# Accessories.net
KiCad netlist of a schematic drawn in Altium Designer
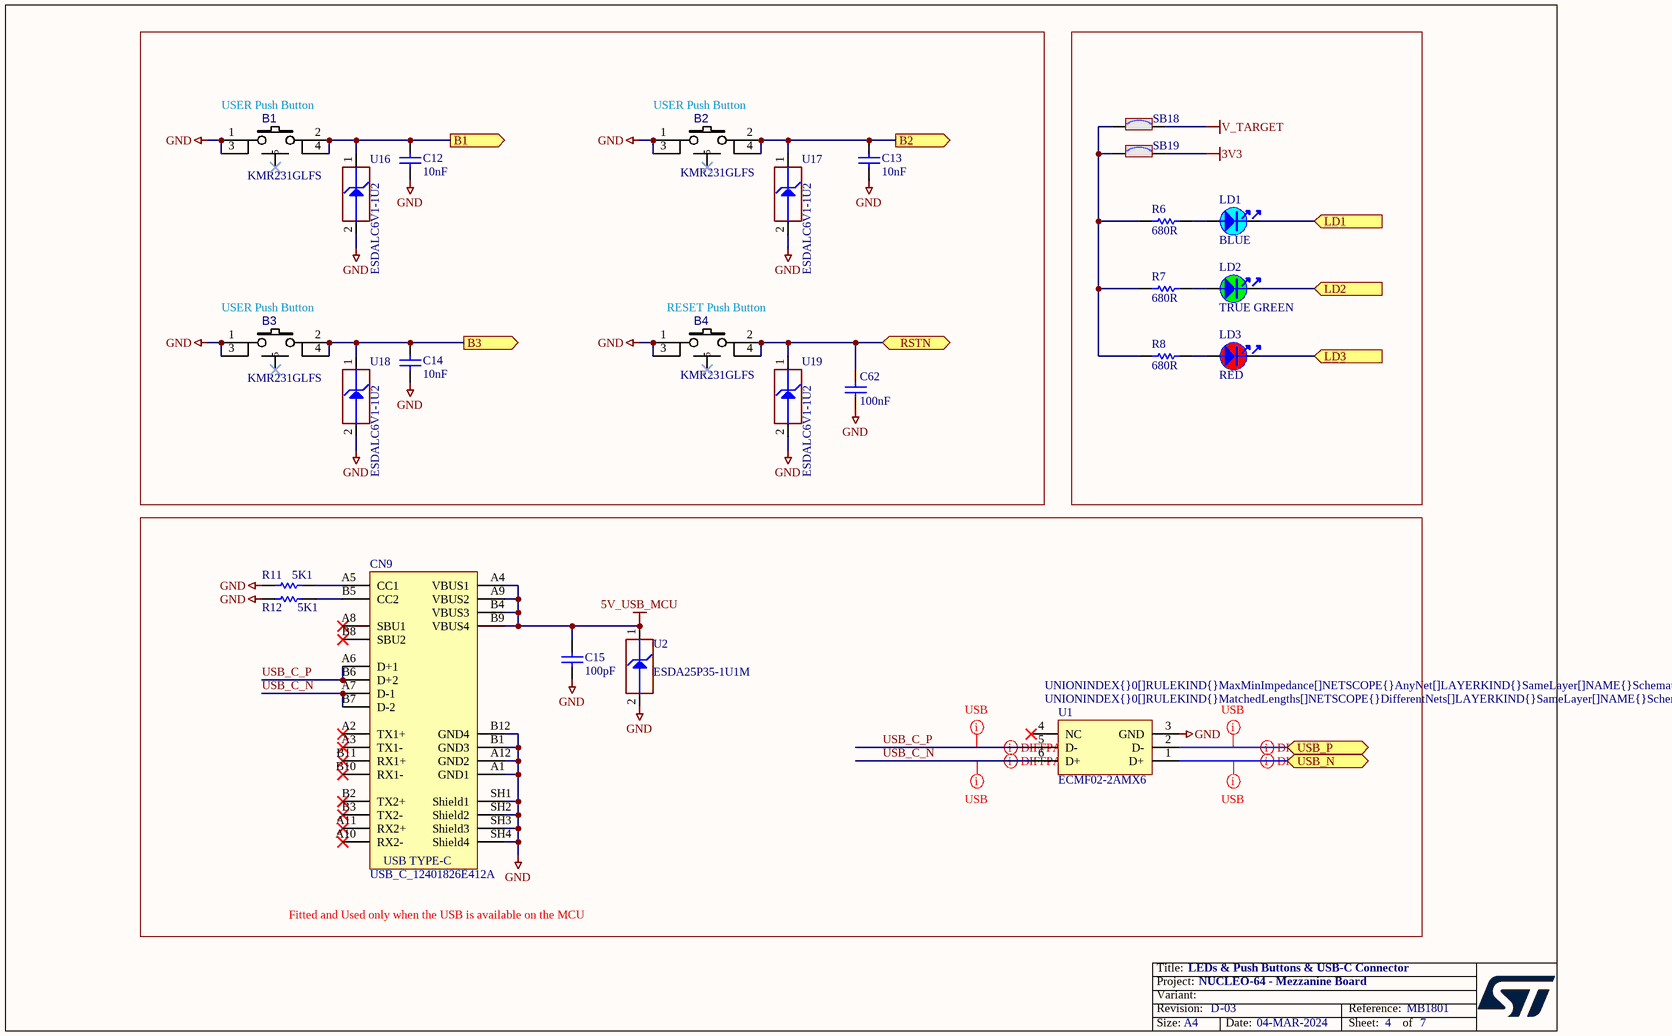
[diagram p0: Accessories.SchDoc]

(export (version "E")
  (design (tool "Eeschema 10.0.6"))
  (components
    (comp (ref "B1")
      (value "KMR231GLFS")
      (footprint "MCD_PARTS:SWI_C&K_Y78B23110FP__ITT_KMR231GLFS")
      (description "Microminiature Tact Switch for SMT - KMR 2 Series - 1.9 mm height")
      (fields (field (name "INTERNAL_PART_NUMBER") "MCD-01485") (field (name "MANUFACTURER") "C&K"))
      (libsource (lib "MCD_PARTS_database") (part "SW-PUSH-CMS_KMR2_BLACK"))
    )
    (comp (ref "B2")
      (value "KMR231GLFS")
      (footprint "MCD_PARTS:SWI_C&K_Y78B23110FP__ITT_KMR231GLFS")
      (description "Microminiature Tact Switch for SMT - KMR 2 Series - 1.9 mm height")
      (fields (field (name "INTERNAL_PART_NUMBER") "MCD-01485") (field (name "MANUFACTURER") "C&K"))
      (libsource (lib "MCD_PARTS_database") (part "SW-PUSH-CMS_KMR2_BLACK"))
    )
    (comp (ref "B3")
      (value "KMR231GLFS")
      (footprint "MCD_PARTS:SWI_C&K_Y78B23110FP__ITT_KMR231GLFS")
      (description "Microminiature Tact Switch for SMT - KMR 2 Series - 1.9 mm height")
      (fields (field (name "INTERNAL_PART_NUMBER") "MCD-01485") (field (name "MANUFACTURER") "C&K"))
      (libsource (lib "MCD_PARTS_database") (part "SW-PUSH-CMS_KMR2_BLACK"))
    )
    (comp (ref "B4")
      (value "KMR231GLFS")
      (footprint "MCD_PARTS:SWI_C&K_Y78B23110FP__ITT_KMR231GLFS")
      (description "Microminiature Tact Switch for SMT - KMR 2 Series - 1.9 mm height")
      (fields (field (name "INTERNAL_PART_NUMBER") "MCD-01485") (field (name "MANUFACTURER") "C&K"))
      (libsource (lib "MCD_PARTS_database") (part "SW-PUSH-CMS_KMR2_BLACK"))
    )
    (comp (ref "C12")
      (value "10nF")
      (footprint "MCD_PARTS:C0402")
      (description "Capacitor, MLCC, 10nF, 50V, X7R, +/-10%, 0402, T=0.5mm")
      (fields (field (name "INTERNAL_PART_NUMBER") "MCD-02198") (field (name "MANUFACTURER") "YAGEO"))
      (libsource (lib "MCD_PARTS_database") (part "Capacitor"))
    )
    (comp (ref "C13")
      (value "10nF")
      (footprint "MCD_PARTS:C0402")
      (description "Capacitor, MLCC, 10nF, 50V, X7R, +/-10%, 0402, T=0.5mm")
      (fields (field (name "INTERNAL_PART_NUMBER") "MCD-02198") (field (name "MANUFACTURER") "YAGEO"))
      (libsource (lib "MCD_PARTS_database") (part "Capacitor"))
    )
    (comp (ref "C14")
      (value "10nF")
      (footprint "MCD_PARTS:C0402")
      (description "Capacitor, MLCC, 10nF, 50V, X7R, +/-10%, 0402, T=0.5mm")
      (fields (field (name "INTERNAL_PART_NUMBER") "MCD-02198") (field (name "MANUFACTURER") "YAGEO"))
      (libsource (lib "MCD_PARTS_database") (part "Capacitor"))
    )
    (comp (ref "C15")
      (value "100pF")
      (footprint "MCD_PARTS:C0402")
      (description "Capacitor, MLCC, 100pF, 50V, NPO, +/-5%, 0402, T=0.5mm")
      (fields
        (field (name "INTERNAL_PART_NUMBER") "MCD-00205")
        (field (name "MANUFACTURER_PART_NUMBER") "CC0402JRNPO9BN101")
      )
      (libsource (lib "MCD_PARTS_database") (part "Capacitor"))
    )
    (comp (ref "C62")
      (value "100nF")
      (footprint "C0402")
      (description "Capacitor, MLCC, 100nF, 16V, X7R, 10%, 0402, T=0.5mm")
      (fields
        (field (name "INTERNAL_PART_NUMBER") "MCD-00006")
        (field (name "MANUFACTURER_PART_NUMBER") "CC0402KRX7R7BB104")
        (field (name "PROVIDED_BY") "SUBCO")
      )
      (libsource (lib "MCD_PARTS_database") (part "Capacitor"))
    )
    (comp (ref "CN9")
      (value "USB_C_12401826E412A")
      (footprint "MCD_PARTS:CON_USB-TYPEC_AMPHENOL_12401826E412A")
      (description "USB_TypeC, 24 pins, RA, SMD, T=2.96mm")
      (fields (field (name "INTERNAL_PART_NUMBER") "MCD-03232") (field (name "MANUFACTURER") "AMPHENOL ICC"))
      (libsource (lib "MCD_PARTS_database") (part "USB_TYPE_C_Receptacle"))
    )
    (comp (ref "LD1")
      (value "BLUE")
      (footprint "MCD_PARTS:LED_0603_VISHAY_VLMB1300-GS08_BLUE_1A2K_H0P8")
      (description "LED Blue, 0603 SMD, 3.3 V Forward Voltage")
      (fields
        (field (name "INTERNAL_PART_NUMBER") "MCD-00584")
        (field (name "MANUFACTURER_PART_NUMBER") "VLMB1300-GS08")
      )
      (libsource (lib "MCD_PARTS_database") (part "LED_blue"))
    )
    (comp (ref "LD2")
      (value "TRUE GREEN")
      (footprint "MCD_PARTS:LED_0603_VISHAY_VLMTG1300-GS08_GREEN_1A2K_H0P8")
      (description "LED Green, 0603 SMD, Fw Voltage = 2.8V - 3.6V")
      (fields
        (field (name "INTERNAL_PART_NUMBER") "MCD-00589")
        (field (name "MANUFACTURER_PART_NUMBER") "VLMTG1300-GS08")
      )
      (libsource (lib "MCD_PARTS_database") (part "LED_green"))
    )
    (comp (ref "LD3")
      (value "RED")
      (footprint "MCD_PARTS:LED_0603_VISHAY_VLMS1300-GS08_RED_1A2K_H0P8")
      (description "LED Red, 0603 SMD, 2V Forward Voltage")
      (fields
        (field (name "INTERNAL_PART_NUMBER") "MCD-00587")
        (field (name "MANUFACTURER_PART_NUMBER") "VLMS1300-GS08")
      )
      (libsource (lib "MCD_PARTS_database") (part "LED_red"))
    )
    (comp (ref "R6")
      (value "680R")
      (footprint "MCD_PARTS:R0402")
      (description "Resistor, 680R, 0402, +/-1%, 1/16W")
      (fields
        (field (name "INTERNAL_PART_NUMBER") "MCD-00507")
        (field (name "MANUFACTURER_PART_NUMBER") "RC0402FR-07680RL")
      )
      (libsource (lib "MCD_PARTS_database") (part "Resistor"))
    )
    (comp (ref "R7")
      (value "680R")
      (footprint "MCD_PARTS:R0402")
      (description "Resistor, 680R, 0402, +/-1%, 1/16W")
      (fields
        (field (name "INTERNAL_PART_NUMBER") "MCD-00507")
        (field (name "MANUFACTURER_PART_NUMBER") "RC0402FR-07680RL")
      )
      (libsource (lib "MCD_PARTS_database") (part "Resistor"))
    )
    (comp (ref "R8")
      (value "680R")
      (footprint "MCD_PARTS:R0402")
      (description "Resistor, 680R, 0402, +/-1%, 1/16W")
      (fields
        (field (name "INTERNAL_PART_NUMBER") "MCD-00507")
        (field (name "MANUFACTURER_PART_NUMBER") "RC0402FR-07680RL")
      )
      (libsource (lib "MCD_PARTS_database") (part "Resistor"))
    )
    (comp (ref "R11")
      (value "5K1")
      (footprint "MCD_PARTS:R0402")
      (description "Resistor, 5K1, 0402, +/-1%, 1/16W")
      (fields
        (field (name "INTERNAL_PART_NUMBER") "MCD-00333")
        (field (name "MANUFACTURER_PART_NUMBER") "RC0402FR-075K1L")
      )
      (libsource (lib "MCD_PARTS_database") (part "Resistor"))
    )
    (comp (ref "R12")
      (value "5K1")
      (footprint "MCD_PARTS:R0402")
      (description "Resistor, 5K1, 0402, +/-1%, 1/16W")
      (fields
        (field (name "INTERNAL_PART_NUMBER") "MCD-00333")
        (field (name "MANUFACTURER_PART_NUMBER") "RC0402FR-075K1L")
      )
      (libsource (lib "MCD_PARTS_database") (part "Resistor"))
    )
    (comp (ref "SB18")
      (value "SB_ON")
      (footprint "MCD_PARTS:SOLDER-BRIDGE_R0402-0R")
      (description "Solder Bridge 0402 ON")
      (fields (field (name "INTERNAL_PART_NUMBER") "MCD-01618") (field (name "MANUFACTURER") "YAGEO"))
      (libsource (lib "MCD_PARTS_database") (part "SB_ON"))
    )
    (comp (ref "SB19")
      (value "SB_ON")
      (footprint "MCD_PARTS:SOLDER-BRIDGE_R0402-0R")
      (description "Solder Bridge 0402 ON")
      (fields (field (name "INTERNAL_PART_NUMBER") "MCD-01618") (field (name "MANUFACTURER") "YAGEO"))
      (libsource (lib "MCD_PARTS_database") (part "SB_ON"))
    )
    (comp (ref "U1")
      (value "ECMF02-2AMX6")
      (footprint "MCD_PARTS:ESD_QFN-6L_1P7X1P5_P050")
      (description "Common mode filter with ESD protection for USB 2.0 interface")
      (fields
        (field (name "INTERNAL_PART_NUMBER") "MCD-00649")
        (field (name "MANUFACTURER") "STMICROELECTRONICS")
      )
      (libsource (lib "MCD_PARTS_database") (part "ECMF02-2AMX6"))
    )
    (comp (ref "U2")
      (value "ESDA25P35-1U1M")
      (footprint "MCD_PARTS:ESD_QFN1610_2N_1K_2A")
      (description "High power Transient voltage suppressor:25V/35A EOS and ESD transients protection.")
      (fields
        (field (name "INTERNAL_PART_NUMBER") "MCD-01207")
        (field (name "MANUFACTURER") "STMICROELECTRONICS")
      )
      (libsource (lib "MCD_PARTS_database") (part "ESD-TRANSIL"))
    )
    (comp (ref "U16")
      (value "ESDALC6V1-1U2")
      (footprint "ESD_ST0201")
      (description "ESD protection 6V1")
      (fields (field (name "INTERNAL_PART_NUMBER") "MCD-00170") (field (name "BMS_PART_NUMBER") "9151132"))
      (libsource (lib "MCD_PARTS_database") (part "ESD-TRANSIL"))
    )
    (comp (ref "U17")
      (value "ESDALC6V1-1U2")
      (footprint "ESD_ST0201")
      (description "ESD protection 6V1")
      (fields (field (name "INTERNAL_PART_NUMBER") "MCD-00170") (field (name "BMS_PART_NUMBER") "9151132"))
      (libsource (lib "MCD_PARTS_database") (part "ESD-TRANSIL"))
    )
    (comp (ref "U18")
      (value "ESDALC6V1-1U2")
      (footprint "ESD_ST0201")
      (description "ESD protection 6V1")
      (fields (field (name "INTERNAL_PART_NUMBER") "MCD-00170") (field (name "BMS_PART_NUMBER") "9151132"))
      (libsource (lib "MCD_PARTS_database") (part "ESD-TRANSIL"))
    )
    (comp (ref "U19")
      (value "ESDALC6V1-1U2")
      (footprint "ESD_ST0201")
      (description "ESD protection 6V1")
      (fields (field (name "INTERNAL_PART_NUMBER") "MCD-00170") (field (name "BMS_PART_NUMBER") "9151132"))
      (libsource (lib "MCD_PARTS_database") (part "ESD-TRANSIL"))
    )
  )
  (nets
    (net (code "1") (name "/B1") (class "Default")
      (node (ref "B1") (pin "2") (pinfunction "2_2") (pintype "passive"))
      (node (ref "B1") (pin "4") (pinfunction "4_4") (pintype "passive"))
      (node (ref "C12") (pin "2") (pinfunction "2_2") (pintype "passive"))
      (node (ref "U16") (pin "1") (pinfunction "IO1_1") (pintype "passive"))
    )
    (net (code "2") (name "/B2") (class "Default")
      (node (ref "B2") (pin "2") (pinfunction "2_2") (pintype "passive"))
      (node (ref "B2") (pin "4") (pinfunction "4_4") (pintype "passive"))
      (node (ref "C13") (pin "2") (pinfunction "2_2") (pintype "passive"))
      (node (ref "U17") (pin "1") (pinfunction "IO1_1") (pintype "passive"))
    )
    (net (code "3") (name "/B3") (class "Default")
      (node (ref "B3") (pin "2") (pinfunction "2_2") (pintype "passive"))
      (node (ref "B3") (pin "4") (pinfunction "4_4") (pintype "passive"))
      (node (ref "C14") (pin "2") (pinfunction "2_2") (pintype "passive"))
      (node (ref "U18") (pin "1") (pinfunction "IO1_1") (pintype "passive"))
    )
    (net (code "4") (name "/LD1") (class "Default") (node (ref "LD1") (pin "2") (pintype "passive")))
    (net (code "5") (name "/LD2") (class "Default") (node (ref "LD2") (pin "2") (pintype "passive")))
    (net (code "6") (name "/LD3") (class "Default") (node (ref "LD3") (pin "2") (pintype "passive")))
    (net (code "7") (name "/RSTN") (class "Default")
      (node (ref "B4") (pin "2") (pinfunction "2_2") (pintype "passive"))
      (node (ref "B4") (pin "4") (pinfunction "4_4") (pintype "passive"))
      (node (ref "C62") (pin "1") (pinfunction "1_1") (pintype "passive"))
      (node (ref "U19") (pin "1") (pinfunction "IO1_1") (pintype "passive"))
    )
    (net (code "8") (name "/USB_C_N") (class "Default")
      (node (ref "CN9") (pin "A7") (pinfunction "D-1_A7") (pintype "passive"))
      (node (ref "CN9") (pin "B7") (pinfunction "D-2_B7") (pintype "passive"))
      (node (ref "U1") (pin "6") (pinfunction "D+_6") (pintype "passive"))
    )
    (net (code "9") (name "/USB_C_P") (class "Default")
      (node (ref "CN9") (pin "A6") (pinfunction "D+1_A6") (pintype "passive"))
      (node (ref "CN9") (pin "B6") (pinfunction "D+2_B6") (pintype "passive"))
      (node (ref "U1") (pin "5") (pinfunction "D-_5") (pintype "passive"))
    )
    (net (code "10") (name "/USB_N") (class "Default")
      (node (ref "U1") (pin "1") (pinfunction "D+_1") (pintype "passive"))
    )
    (net (code "11") (name "/USB_P") (class "Default")
      (node (ref "U1") (pin "2") (pinfunction "D-_2") (pintype "passive"))
    )
    (net (code "12") (name "3V3") (class "Default")
      (node (ref "SB19") (pin "2") (pinfunction "2_2") (pintype "passive"))
    )
    (net (code "13") (name "5V_USB_MCU") (class "Default")
      (node (ref "C15") (pin "2") (pinfunction "2_2") (pintype "passive"))
      (node (ref "CN9") (pin "A4") (pinfunction "VBUS1_A4") (pintype "passive"))
      (node (ref "CN9") (pin "A9") (pinfunction "VBUS2_A9") (pintype "passive"))
      (node (ref "CN9") (pin "B4") (pinfunction "VBUS3_B4") (pintype "passive"))
      (node (ref "CN9") (pin "B9") (pinfunction "VBUS4_B9") (pintype "passive"))
      (node (ref "U2") (pin "1") (pinfunction "IO1_1") (pintype "passive"))
    )
    (net (code "14") (name "GND") (class "Default")
      (node (ref "B1") (pin "1") (pinfunction "1_1") (pintype "passive"))
      (node (ref "B1") (pin "3") (pinfunction "3_3") (pintype "passive"))
      (node (ref "B2") (pin "1") (pinfunction "1_1") (pintype "passive"))
      (node (ref "B2") (pin "3") (pinfunction "3_3") (pintype "passive"))
      (node (ref "B3") (pin "1") (pinfunction "1_1") (pintype "passive"))
      (node (ref "B3") (pin "3") (pinfunction "3_3") (pintype "passive"))
      (node (ref "B4") (pin "1") (pinfunction "1_1") (pintype "passive"))
      (node (ref "B4") (pin "3") (pinfunction "3_3") (pintype "passive"))
      (node (ref "C12") (pin "1") (pinfunction "1_1") (pintype "passive"))
      (node (ref "C13") (pin "1") (pinfunction "1_1") (pintype "passive"))
      (node (ref "C14") (pin "1") (pinfunction "1_1") (pintype "passive"))
      (node (ref "C15") (pin "1") (pinfunction "1_1") (pintype "passive"))
      (node (ref "C62") (pin "2") (pinfunction "2_2") (pintype "passive"))
      (node (ref "CN9") (pin "A1") (pinfunction "GND1_A1") (pintype "passive"))
      (node (ref "CN9") (pin "A12") (pinfunction "GND2_A12") (pintype "passive"))
      (node (ref "CN9") (pin "B1") (pinfunction "GND3_B1") (pintype "passive"))
      (node (ref "CN9") (pin "B12") (pinfunction "GND4_B12") (pintype "passive"))
      (node (ref "CN9") (pin "SH1") (pinfunction "Shield1_SH1") (pintype "passive"))
      (node (ref "CN9") (pin "SH2") (pinfunction "Shield2_SH2") (pintype "passive"))
      (node (ref "CN9") (pin "SH3") (pinfunction "Shield3_SH3") (pintype "passive"))
      (node (ref "CN9") (pin "SH4") (pinfunction "Shield4_SH4") (pintype "passive"))
      (node (ref "R11") (pin "1") (pinfunction "1_1") (pintype "passive"))
      (node (ref "R12") (pin "1") (pinfunction "1_1") (pintype "passive"))
      (node (ref "U1") (pin "3") (pinfunction "GND_3") (pintype "passive"))
      (node (ref "U16") (pin "2") (pinfunction "GND_2") (pintype "passive"))
      (node (ref "U17") (pin "2") (pinfunction "GND_2") (pintype "passive"))
      (node (ref "U18") (pin "2") (pinfunction "GND_2") (pintype "passive"))
      (node (ref "U19") (pin "2") (pinfunction "GND_2") (pintype "passive"))
      (node (ref "U2") (pin "2") (pinfunction "GND_2") (pintype "passive"))
    )
    (net (code "15") (name "Net-(CN9-CC1)") (class "Default")
      (node (ref "CN9") (pin "A5") (pinfunction "CC1_A5") (pintype "passive"))
      (node (ref "R11") (pin "2") (pinfunction "2_2") (pintype "passive"))
    )
    (net (code "16") (name "Net-(CN9-CC2)") (class "Default")
      (node (ref "CN9") (pin "B5") (pinfunction "CC2_B5") (pintype "passive"))
      (node (ref "R12") (pin "2") (pinfunction "2_2") (pintype "passive"))
    )
    (net (code "17") (name "Net-(LD1-Pad1)") (class "Default")
      (node (ref "LD1") (pin "1") (pintype "passive"))
      (node (ref "R6") (pin "2") (pinfunction "2_2") (pintype "passive"))
    )
    (net (code "18") (name "Net-(LD2-Pad1)") (class "Default")
      (node (ref "LD2") (pin "1") (pintype "passive"))
      (node (ref "R7") (pin "2") (pinfunction "2_2") (pintype "passive"))
    )
    (net (code "19") (name "Net-(LD3-Pad1)") (class "Default")
      (node (ref "LD3") (pin "1") (pintype "passive"))
      (node (ref "R8") (pin "2") (pinfunction "2_2") (pintype "passive"))
    )
    (net (code "20") (name "Net-(R6-Pad1)") (class "Default")
      (node (ref "R6") (pin "1") (pinfunction "1_1") (pintype "passive"))
      (node (ref "R7") (pin "1") (pinfunction "1_1") (pintype "passive"))
      (node (ref "R8") (pin "1") (pinfunction "1_1") (pintype "passive"))
      (node (ref "SB18") (pin "1") (pinfunction "1_1") (pintype "passive"))
      (node (ref "SB19") (pin "1") (pinfunction "1_1") (pintype "passive"))
    )
    (net (code "21") (name "V_TARGET") (class "Default")
      (node (ref "SB18") (pin "2") (pinfunction "2_2") (pintype "passive"))
    )
    (net (code "22") (name "unconnected-(B1-Pad5)") (class "Default")
      (node (ref "B1") (pin "5") (pinfunction "5_5") (pintype "passive+no_connect"))
    )
    (net (code "23") (name "unconnected-(B2-Pad5)") (class "Default")
      (node (ref "B2") (pin "5") (pinfunction "5_5") (pintype "passive+no_connect"))
    )
    (net (code "24") (name "unconnected-(B3-Pad5)") (class "Default")
      (node (ref "B3") (pin "5") (pinfunction "5_5") (pintype "passive+no_connect"))
    )
    (net (code "25") (name "unconnected-(B4-Pad5)") (class "Default")
      (node (ref "B4") (pin "5") (pinfunction "5_5") (pintype "passive+no_connect"))
    )
    (net (code "26") (name "unconnected-(CN9-RX1+-PadB11)") (class "Default")
      (node (ref "CN9") (pin "B11") (pinfunction "RX1+_B11") (pintype "passive+no_connect"))
    )
    (net (code "27") (name "unconnected-(CN9-RX1--PadB10)") (class "Default")
      (node (ref "CN9") (pin "B10") (pinfunction "RX1-_B10") (pintype "passive+no_connect"))
    )
    (net (code "28") (name "unconnected-(CN9-RX2+-PadA11)") (class "Default")
      (node (ref "CN9") (pin "A11") (pinfunction "RX2+_A11") (pintype "passive+no_connect"))
    )
    (net (code "29") (name "unconnected-(CN9-RX2--PadA10)") (class "Default")
      (node (ref "CN9") (pin "A10") (pinfunction "RX2-_A10") (pintype "passive+no_connect"))
    )
    (net (code "30") (name "unconnected-(CN9-SBU1-PadA8)") (class "Default")
      (node (ref "CN9") (pin "A8") (pinfunction "SBU1_A8") (pintype "passive+no_connect"))
    )
    (net (code "31") (name "unconnected-(CN9-SBU2-PadB8)") (class "Default")
      (node (ref "CN9") (pin "B8") (pinfunction "SBU2_B8") (pintype "passive+no_connect"))
    )
    (net (code "32") (name "unconnected-(CN9-TX1+-PadA2)") (class "Default")
      (node (ref "CN9") (pin "A2") (pinfunction "TX1+_A2") (pintype "passive+no_connect"))
    )
    (net (code "33") (name "unconnected-(CN9-TX1--PadA3)") (class "Default")
      (node (ref "CN9") (pin "A3") (pinfunction "TX1-_A3") (pintype "passive+no_connect"))
    )
    (net (code "34") (name "unconnected-(CN9-TX2+-PadB2)") (class "Default")
      (node (ref "CN9") (pin "B2") (pinfunction "TX2+_B2") (pintype "passive+no_connect"))
    )
    (net (code "35") (name "unconnected-(CN9-TX2--PadB3)") (class "Default")
      (node (ref "CN9") (pin "B3") (pinfunction "TX2-_B3") (pintype "passive+no_connect"))
    )
    (net (code "36") (name "unconnected-(U1-NC-Pad4)") (class "Default")
      (node (ref "U1") (pin "4") (pinfunction "NC_4") (pintype "passive+no_connect"))
    )
  )
)
